# Op.net
KiCad netlist of a schematic drawn in Altium Designer
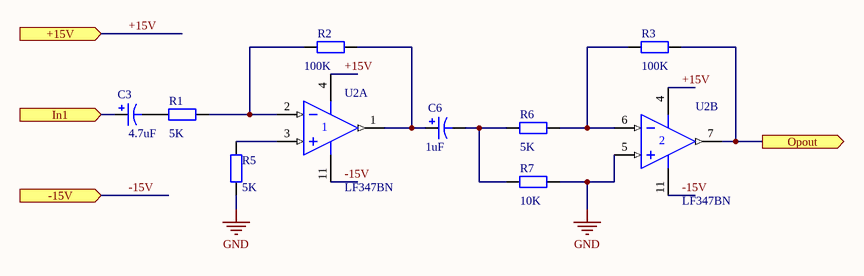
[diagram p0: Op.SchDoc]

(export (version "E")
  (design (tool "Eeschema 10.0.6"))
  (components
    (comp (ref "C3")
      (value "4.7uF")
      (footprint "RB7.6-15")
      (description "Polarized Capacitor (Radial)")
      (fields (field (name "Comment") "Cap Pol1") (field (name "PUBLISHER") "Altium Limited"))
      (libsource (lib "Miscellaneous Devices") (part "Cap Pol1"))
    )
    (comp (ref "C6")
      (value "1uF")
      (footprint "RB7.6-15")
      (description "Polarized Capacitor (Radial)")
      (fields (field (name "Comment") "Cap Pol1") (field (name "PUBLISHER") "Altium Limited"))
      (libsource (lib "Miscellaneous Devices") (part "Cap Pol1"))
    )
    (comp (ref "R1")
      (value "5K")
      (footprint "AXIAL-0.4")
      (description "Resistor")
      (fields (field (name "Comment") "Res2") (field (name "PUBLISHER") "Altium Limited"))
      (libsource (lib "Miscellaneous Devices") (part "Res2"))
    )
    (comp (ref "R2")
      (value "100K")
      (footprint "AXIAL-0.4")
      (description "Resistor")
      (fields (field (name "Comment") "Res2") (field (name "PUBLISHER") "Altium Limited"))
      (libsource (lib "") (part "Res2_1"))
    )
    (comp (ref "R3")
      (value "100K")
      (footprint "AXIAL-0.4")
      (description "Resistor")
      (fields (field (name "Comment") "Res2") (field (name "PUBLISHER") "Altium Limited"))
      (libsource (lib "") (part "Res2_1"))
    )
    (comp (ref "R5")
      (value "5K")
      (footprint "AXIAL-0.4")
      (description "Resistor")
      (fields (field (name "Comment") "Res2") (field (name "PUBLISHER") "Altium Limited"))
      (libsource (lib "") (part "Res2_2"))
    )
    (comp (ref "R6")
      (value "5K")
      (footprint "AXIAL-0.4")
      (description "Resistor")
      (fields (field (name "Comment") "Res2") (field (name "PUBLISHER") "Altium Limited"))
      (libsource (lib "") (part "Res2_1"))
    )
    (comp (ref "R7")
      (value "10K")
      (footprint "AXIAL-0.4")
      (description "Resistor")
      (fields (field (name "Comment") "Res2") (field (name "PUBLISHER") "Altium Limited"))
      (libsource (lib "") (part "Res2_1"))
    )
    (comp (ref "U2")
      (value "LF347BN")
      (footprint "N14A")
      (description "Wide-Bandwidth Quad JFET Input Operational Amplifier")
      (fields (field (name "PUBLISHER") "Altium Limited"))
      (libsource (lib "NSC Operational Amplifier") (part "LF347BN"))
    )
  )
  (nets
    (net (code "1") (name "/+15V") (class "Default")
      (node (ref "U2") (pin "4") (pinfunction "V+_4") (pintype "power_in"))
    )
    (net (code "2") (name "/-15V") (class "Default")
      (node (ref "U2") (pin "11") (pinfunction "V-_11") (pintype "power_in"))
    )
    (net (code "3") (name "/In1") (class "Default")
      (node (ref "C3") (pin "1") (pinfunction "1_1") (pintype "passive"))
    )
    (net (code "4") (name "/Opout") (class "Default")
      (node (ref "R3") (pin "2") (pinfunction "2_2") (pintype "passive"))
      (node (ref "U2") (pin "7") (pinfunction "OUT_7") (pintype "output"))
    )
    (net (code "5") (name "GND") (class "Default")
      (node (ref "R5") (pin "1") (pinfunction "1_1") (pintype "passive"))
      (node (ref "R7") (pin "2") (pinfunction "2_2") (pintype "passive"))
      (node (ref "U2") (pin "5") (pinfunction "IN+_5") (pintype "input"))
    )
    (net (code "6") (name "Net-(C3-Pad2)") (class "Default")
      (node (ref "C3") (pin "2") (pinfunction "2_2") (pintype "passive"))
      (node (ref "R1") (pin "2") (pinfunction "2_2") (pintype "passive"))
    )
    (net (code "7") (name "Net-(C6-Pad2)") (class "Default")
      (node (ref "C6") (pin "2") (pinfunction "2_2") (pintype "passive"))
      (node (ref "R6") (pin "1") (pinfunction "1_1") (pintype "passive"))
      (node (ref "R7") (pin "1") (pinfunction "1_1") (pintype "passive"))
    )
    (net (code "8") (name "Net-(U2A-IN+)") (class "Default")
      (node (ref "R5") (pin "2") (pinfunction "2_2") (pintype "passive"))
      (node (ref "U2") (pin "3") (pinfunction "IN+_3") (pintype "input"))
    )
    (net (code "9") (name "Net-(U2A-IN-)") (class "Default")
      (node (ref "R1") (pin "1") (pinfunction "1_1") (pintype "passive"))
      (node (ref "R2") (pin "1") (pinfunction "1_1") (pintype "passive"))
      (node (ref "U2") (pin "2") (pinfunction "IN-_2") (pintype "input"))
    )
    (net (code "10") (name "Net-(U2A-OUT)") (class "Default")
      (node (ref "C6") (pin "1") (pinfunction "1_1") (pintype "passive"))
      (node (ref "R2") (pin "2") (pinfunction "2_2") (pintype "passive"))
      (node (ref "U2") (pin "1") (pinfunction "OUT_1") (pintype "output"))
    )
    (net (code "11") (name "Net-(U2B-IN-)") (class "Default")
      (node (ref "R3") (pin "1") (pinfunction "1_1") (pintype "passive"))
      (node (ref "R6") (pin "2") (pinfunction "2_2") (pintype "passive"))
      (node (ref "U2") (pin "6") (pinfunction "IN-_6") (pintype "input"))
    )
  )
)
